# 12v-dual_and_5v_v1_2.net
KiCad netlist of a schematic drawn in EAGLE
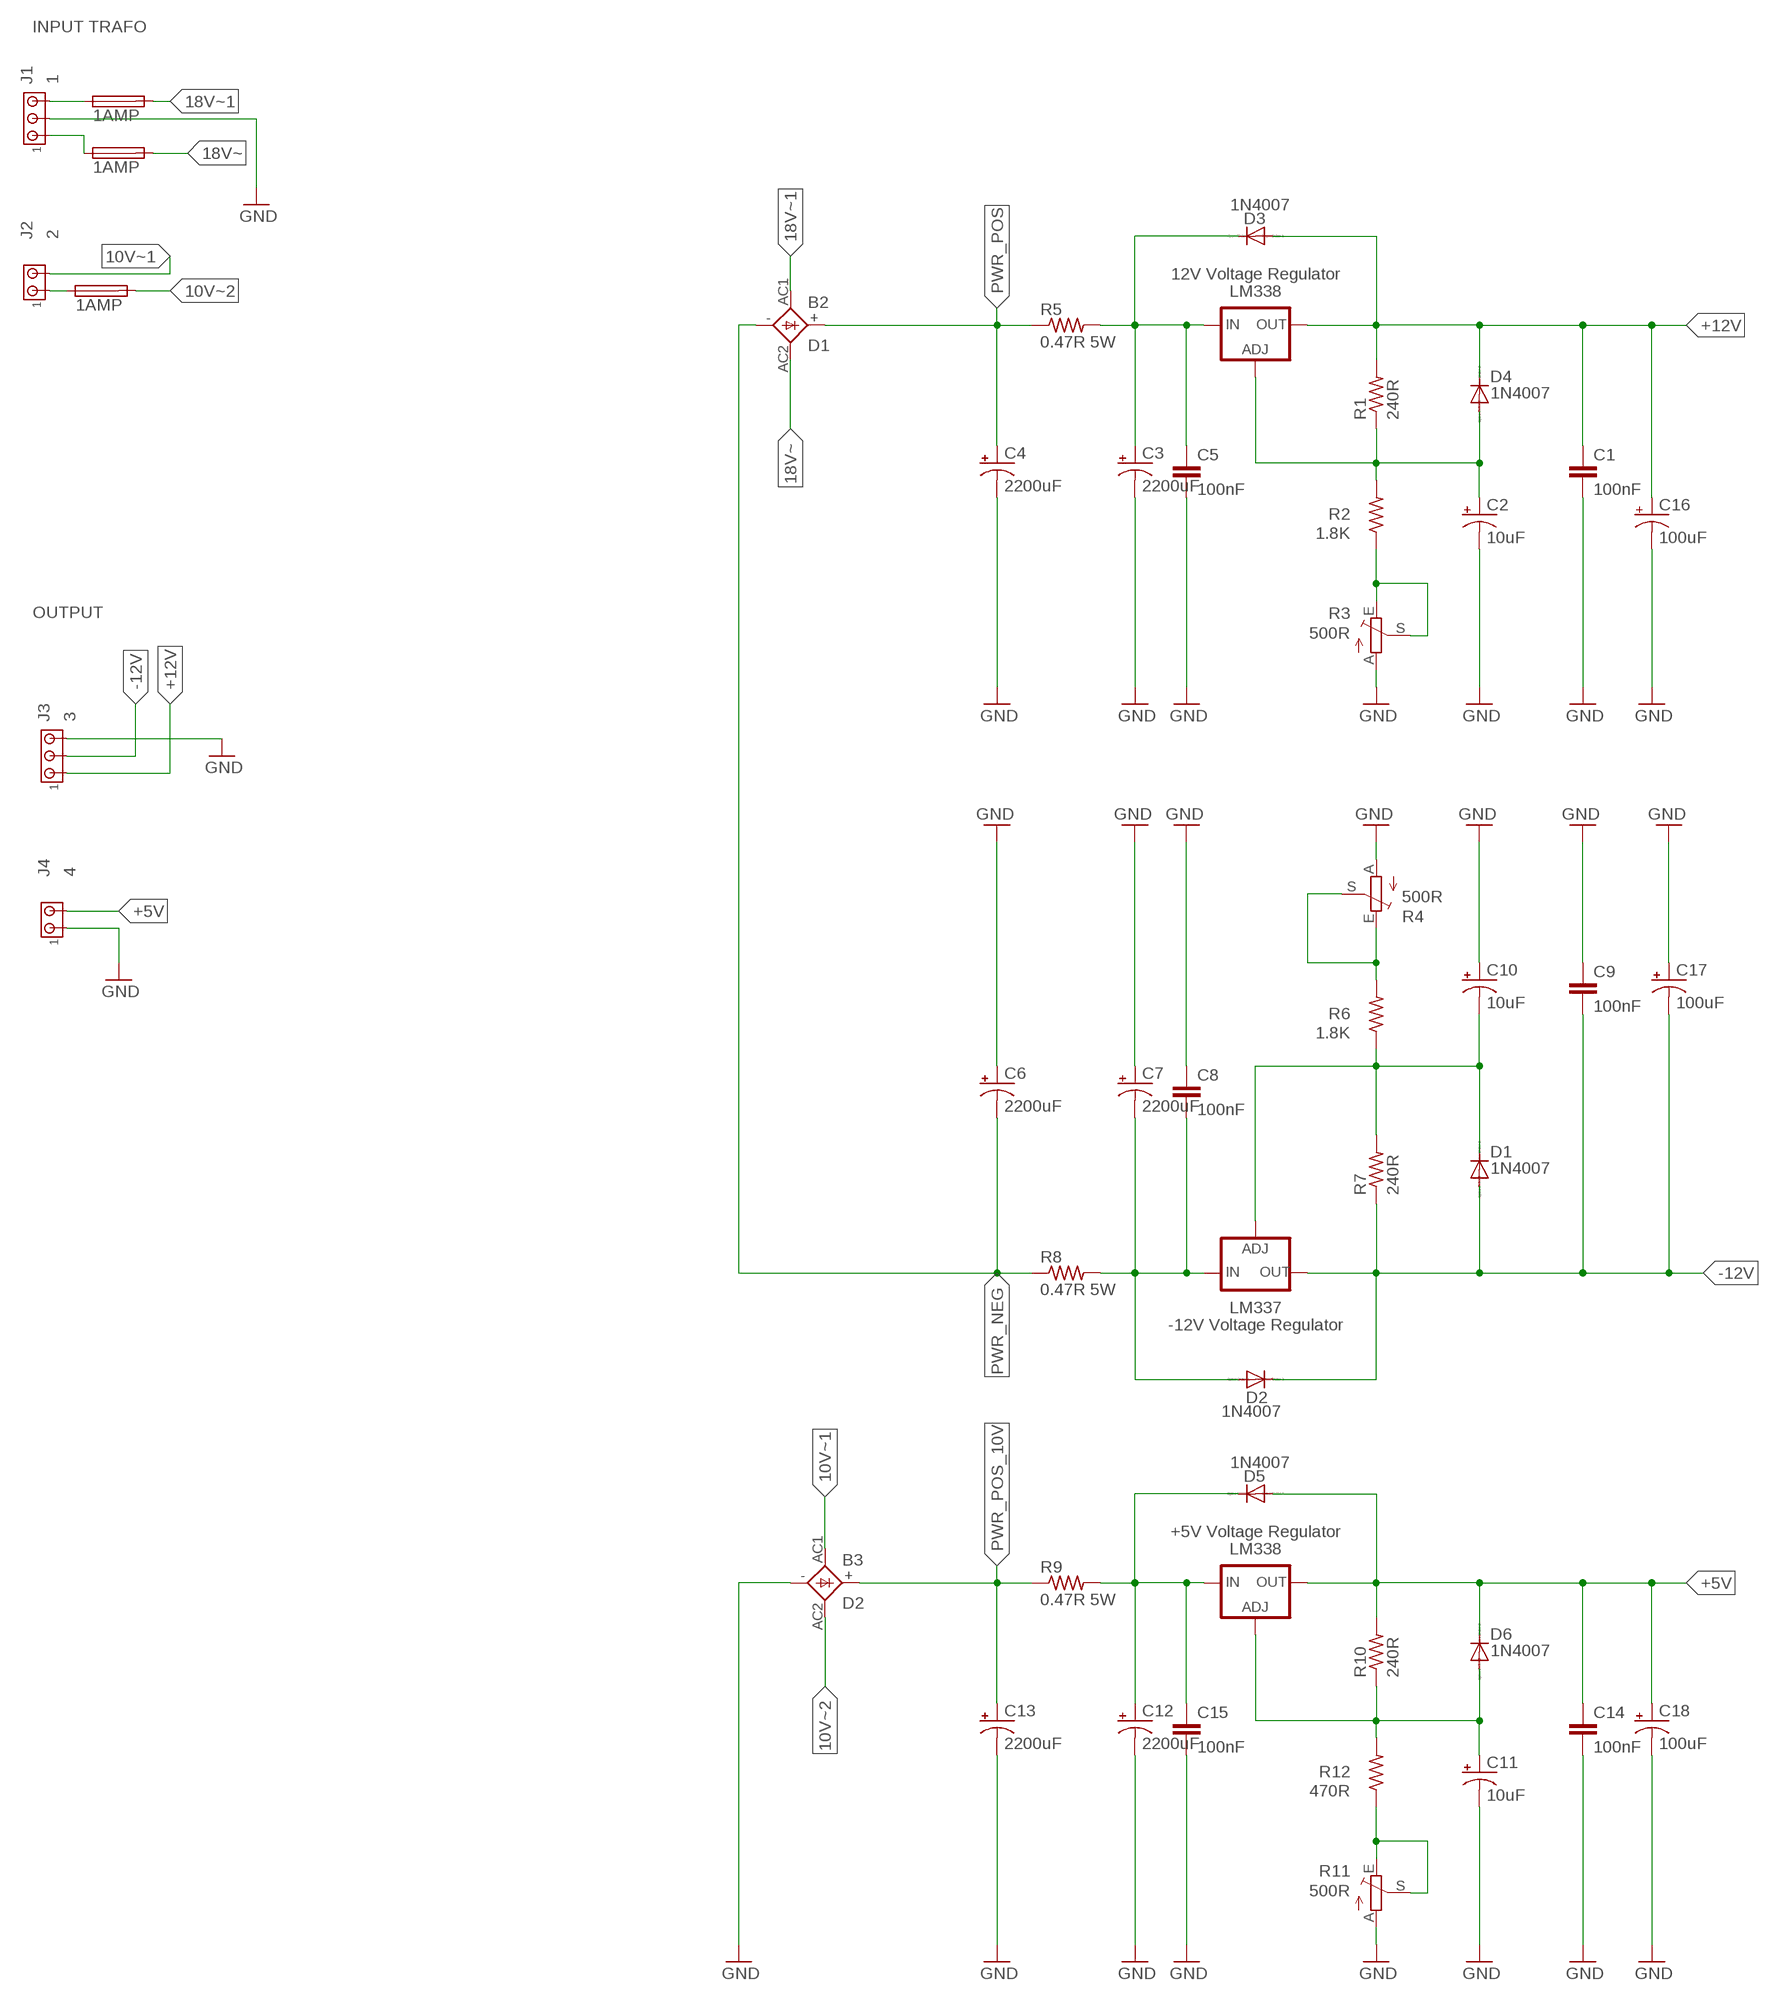
[diagram p0: schematic, sheet 1]

(export (version "E")
  (design (tool "Eeschema 10.0.6"))
  (components
    (comp (ref "B2")
      (value "D1")
      (footprint "eagle-import:FB15")
      (libsource (lib "eagle-import") (part "FB15"))
    )
    (comp (ref "B3")
      (value "D2")
      (footprint "eagle-import:FB15")
      (libsource (lib "eagle-import") (part "FB15"))
    )
    (comp (ref "C1")
      (value "100nF")
      (footprint "eagle-import:C050-025X075")
      (libsource (lib "eagle-import") (part "C-EU050-025X075"))
    )
    (comp (ref "C2")
      (value "10uF")
      (footprint "eagle-import:E2-5")
      (libsource (lib "eagle-import") (part "CPOL-USE2-5"))
    )
    (comp (ref "C3")
      (value "2200uF")
      (footprint "eagle-import:E5-13")
      (libsource (lib "eagle-import") (part "CPOL-USE5-13"))
    )
    (comp (ref "C4")
      (value "2200uF")
      (footprint "eagle-import:E5-13")
      (libsource (lib "eagle-import") (part "CPOL-USE5-13"))
    )
    (comp (ref "C5")
      (value "100nF")
      (footprint "eagle-import:C050-025X075")
      (libsource (lib "eagle-import") (part "C-EU050-025X075"))
    )
    (comp (ref "C6")
      (value "2200uF")
      (footprint "eagle-import:E5-13")
      (libsource (lib "eagle-import") (part "CPOL-USE5-13"))
    )
    (comp (ref "C7")
      (value "2200uF")
      (footprint "eagle-import:E5-13")
      (libsource (lib "eagle-import") (part "CPOL-USE5-13"))
    )
    (comp (ref "C8")
      (value "100nF")
      (footprint "eagle-import:C050-025X075")
      (libsource (lib "eagle-import") (part "C-EU050-025X075"))
    )
    (comp (ref "C9")
      (value "100nF")
      (footprint "eagle-import:C050-025X075")
      (libsource (lib "eagle-import") (part "C-EU050-025X075"))
    )
    (comp (ref "C10")
      (value "10uF")
      (footprint "eagle-import:E2-5")
      (libsource (lib "eagle-import") (part "CPOL-USE2-5"))
    )
    (comp (ref "C11")
      (value "10uF")
      (footprint "eagle-import:E2-5")
      (libsource (lib "eagle-import") (part "CPOL-USE2-5"))
    )
    (comp (ref "C12")
      (value "2200uF")
      (footprint "eagle-import:E5-13")
      (libsource (lib "eagle-import") (part "CPOL-USE5-13"))
    )
    (comp (ref "C13")
      (value "2200uF")
      (footprint "eagle-import:E5-13")
      (libsource (lib "eagle-import") (part "CPOL-USE5-13"))
    )
    (comp (ref "C14")
      (value "100nF")
      (footprint "eagle-import:C050-025X075")
      (libsource (lib "eagle-import") (part "C-EU050-025X075"))
    )
    (comp (ref "C15")
      (value "100nF")
      (footprint "eagle-import:C050-025X075")
      (libsource (lib "eagle-import") (part "C-EU050-025X075"))
    )
    (comp (ref "C16")
      (value "100uF")
      (footprint "eagle-import:E2-5")
      (libsource (lib "eagle-import") (part "CPOL-USE2-5"))
    )
    (comp (ref "C17")
      (value "100uF")
      (footprint "eagle-import:E2-5")
      (libsource (lib "eagle-import") (part "CPOL-USE2-5"))
    )
    (comp (ref "C18")
      (value "100uF")
      (footprint "eagle-import:E2-5")
      (libsource (lib "eagle-import") (part "CPOL-USE2-5"))
    )
    (comp (ref "D1")
      (value "1N4007")
      (footprint "eagle-import:DO41-10")
      (libsource (lib "eagle-import") (part "1N4004"))
    )
    (comp (ref "D2")
      (value "1N4007")
      (footprint "eagle-import:DO41-10")
      (libsource (lib "eagle-import") (part "1N4004"))
    )
    (comp (ref "D3")
      (value "1N4007")
      (footprint "eagle-import:DO41-10")
      (libsource (lib "eagle-import") (part "1N4004"))
    )
    (comp (ref "D4")
      (value "1N4007")
      (footprint "eagle-import:DO41-10")
      (libsource (lib "eagle-import") (part "1N4004"))
    )
    (comp (ref "D5")
      (value "1N4007")
      (footprint "eagle-import:DO41-10")
      (libsource (lib "eagle-import") (part "1N4004"))
    )
    (comp (ref "D6")
      (value "1N4007")
      (footprint "eagle-import:DO41-10")
      (libsource (lib "eagle-import") (part "1N4004"))
    )
    (comp (ref "F1")
      (value "1AMP")
      (footprint "eagle-import:SH25")
      (fields (field (name "MF") "SCHURTER") (field (name "MPN") "0031.8211"))
      (libsource (lib "eagle-import") (part "SH25"))
    )
    (comp (ref "F2")
      (value "1AMP")
      (footprint "eagle-import:SH25")
      (fields (field (name "MF") "SCHURTER") (field (name "MPN") "0031.8211"))
      (libsource (lib "eagle-import") (part "SH25"))
    )
    (comp (ref "F3")
      (value "1AMP")
      (footprint "eagle-import:SH25")
      (fields (field (name "MF") "SCHURTER") (field (name "MPN") "0031.8211"))
      (libsource (lib "eagle-import") (part "SH25"))
    )
    (comp (ref "IC1")
      (value "LM337")
      (footprint "eagle-import:337TS")
      (libsource (lib "eagle-import") (part "LM337TS"))
    )
    (comp (ref "IC2")
      (value "LM338")
      (footprint "eagle-import:317TS")
      (fields (field (name "PARTNUMBER") "LM317M"))
      (libsource (lib "eagle-import") (part "LM317TS"))
    )
    (comp (ref "IC3")
      (value "LM317MB")
      (footprint "eagle-import:317TS")
      (fields (field (name "PARTNUMBER") "LM317M"))
      (libsource (lib "eagle-import") (part "LM317TS"))
    )
    (comp (ref "J1")
      (value "1")
      (footprint "eagle-import:1X3MTA")
      (libsource (lib "eagle-import") (part "MTA03-156"))
    )
    (comp (ref "J2")
      (value "2")
      (footprint "eagle-import:1X2MTA")
      (libsource (lib "eagle-import") (part "MTA02-156"))
    )
    (comp (ref "J3")
      (value "3")
      (footprint "eagle-import:1X3MTA")
      (libsource (lib "eagle-import") (part "MTA03-156"))
    )
    (comp (ref "J4")
      (value "4")
      (footprint "eagle-import:1X2MTA")
      (libsource (lib "eagle-import") (part "MTA02-156"))
    )
    (comp (ref "R1")
      (value "240R")
      (footprint "eagle-import:0204_7")
      (libsource (lib "eagle-import") (part "R-US_0204/7"))
    )
    (comp (ref "R2")
      (value "1.8K")
      (footprint "eagle-import:0204_7")
      (libsource (lib "eagle-import") (part "R-US_0204/7"))
    )
    (comp (ref "R3")
      (value "500R")
      (footprint "eagle-import:RJ9W")
      (libsource (lib "eagle-import") (part "TRIM_EU-RJ9W"))
    )
    (comp (ref "R4")
      (value "500R")
      (footprint "eagle-import:RJ9W")
      (libsource (lib "eagle-import") (part "TRIM_EU-RJ9W"))
    )
    (comp (ref "R5")
      (value "0.47R 5W")
      (footprint "eagle-import:0617_17")
      (libsource (lib "eagle-import") (part "R-US_0617/17"))
    )
    (comp (ref "R6")
      (value "1.8K")
      (footprint "eagle-import:0204_7")
      (libsource (lib "eagle-import") (part "R-US_0204/7"))
    )
    (comp (ref "R7")
      (value "240R")
      (footprint "eagle-import:0204_7")
      (libsource (lib "eagle-import") (part "R-US_0204/7"))
    )
    (comp (ref "R8")
      (value "0.47R 5W")
      (footprint "eagle-import:0617_17")
      (libsource (lib "eagle-import") (part "R-US_0617/17"))
    )
    (comp (ref "R9")
      (value "0.47R 5W")
      (footprint "eagle-import:0617_17")
      (libsource (lib "eagle-import") (part "R-US_0617/17"))
    )
    (comp (ref "R10")
      (value "240R")
      (footprint "eagle-import:0204_7")
      (libsource (lib "eagle-import") (part "R-US_0204/7"))
    )
    (comp (ref "R11")
      (value "500R")
      (footprint "eagle-import:RJ9W")
      (libsource (lib "eagle-import") (part "TRIM_EU-RJ9W"))
    )
    (comp (ref "R12")
      (value "470R")
      (footprint "eagle-import:0204_7")
      (libsource (lib "eagle-import") (part "R-US_0204/7"))
    )
  )
  (nets
    (net (code "1") (name "+5V") (class "Default")
      (node (ref "C14") (pin "1") (pinfunction "1_1") (pintype "passive"))
      (node (ref "C18") (pin "+") (pinfunction "+_+") (pintype "passive"))
      (node (ref "D5") (pin "A") (pinfunction "A_A") (pintype "passive"))
      (node (ref "D6") (pin "C") (pinfunction "C_C") (pintype "passive"))
      (node (ref "IC3") (pin "2") (pinfunction "OUT_2") (pintype "passive"))
      (node (ref "J4") (pin "2") (pinfunction "2_2") (pintype "passive"))
      (node (ref "R10") (pin "2") (pinfunction "2_2") (pintype "passive"))
    )
    (net (code "2") (name "+12V") (class "Default")
      (node (ref "C1") (pin "1") (pinfunction "1_1") (pintype "passive"))
      (node (ref "C16") (pin "+") (pinfunction "+_+") (pintype "passive"))
      (node (ref "D3") (pin "A") (pinfunction "A_A") (pintype "passive"))
      (node (ref "D4") (pin "C") (pinfunction "C_C") (pintype "passive"))
      (node (ref "IC2") (pin "2") (pinfunction "OUT_2") (pintype "passive"))
      (node (ref "J3") (pin "1") (pinfunction "1_1") (pintype "passive"))
      (node (ref "R1") (pin "2") (pinfunction "2_2") (pintype "passive"))
    )
    (net (code "3") (name "-12V") (class "Default")
      (node (ref "C17") (pin "-") (pinfunction "-_-") (pintype "passive"))
      (node (ref "C9") (pin "2") (pinfunction "2_2") (pintype "passive"))
      (node (ref "D1") (pin "A") (pinfunction "A_A") (pintype "passive"))
      (node (ref "D2") (pin "C") (pinfunction "C_C") (pintype "passive"))
      (node (ref "IC1") (pin "3") (pinfunction "OUT_3") (pintype "passive"))
      (node (ref "J3") (pin "2") (pinfunction "2_2") (pintype "passive"))
      (node (ref "R7") (pin "1") (pinfunction "1_1") (pintype "passive"))
    )
    (net (code "4") (name "/10V~{1}") (class "Default")
      (node (ref "B3") (pin "AC1") (pinfunction "AC1_AC1") (pintype "passive"))
      (node (ref "J2") (pin "2") (pinfunction "2_2") (pintype "passive"))
    )
    (net (code "5") (name "/10V~{2}") (class "Default")
      (node (ref "B3") (pin "AC2") (pinfunction "AC2_AC2") (pintype "passive"))
      (node (ref "F3") (pin "2") (pinfunction "2_2") (pintype "passive"))
    )
    (net (code "6") (name "/18V~{1}") (class "Default")
      (node (ref "B2") (pin "AC1") (pinfunction "AC1_AC1") (pintype "passive"))
      (node (ref "F1") (pin "2") (pinfunction "2_2") (pintype "passive"))
    )
    (net (code "7") (name "/18V~{}") (class "Default")
      (node (ref "B2") (pin "AC2") (pinfunction "AC2_AC2") (pintype "passive"))
      (node (ref "F2") (pin "2") (pinfunction "2_2") (pintype "passive"))
    )
    (net (code "8") (name "GND") (class "Default")
      (node (ref "B3") (pin "-") (pinfunction "-_-") (pintype "passive"))
      (node (ref "C1") (pin "2") (pinfunction "2_2") (pintype "passive"))
      (node (ref "C10") (pin "+") (pinfunction "+_+") (pintype "passive"))
      (node (ref "C11") (pin "-") (pinfunction "-_-") (pintype "passive"))
      (node (ref "C12") (pin "-") (pinfunction "-_-") (pintype "passive"))
      (node (ref "C13") (pin "-") (pinfunction "-_-") (pintype "passive"))
      (node (ref "C14") (pin "2") (pinfunction "2_2") (pintype "passive"))
      (node (ref "C15") (pin "2") (pinfunction "2_2") (pintype "passive"))
      (node (ref "C16") (pin "-") (pinfunction "-_-") (pintype "passive"))
      (node (ref "C17") (pin "+") (pinfunction "+_+") (pintype "passive"))
      (node (ref "C18") (pin "-") (pinfunction "-_-") (pintype "passive"))
      (node (ref "C2") (pin "-") (pinfunction "-_-") (pintype "passive"))
      (node (ref "C3") (pin "-") (pinfunction "-_-") (pintype "passive"))
      (node (ref "C4") (pin "-") (pinfunction "-_-") (pintype "passive"))
      (node (ref "C5") (pin "2") (pinfunction "2_2") (pintype "passive"))
      (node (ref "C6") (pin "+") (pinfunction "+_+") (pintype "passive"))
      (node (ref "C7") (pin "+") (pinfunction "+_+") (pintype "passive"))
      (node (ref "C8") (pin "1") (pinfunction "1_1") (pintype "passive"))
      (node (ref "C9") (pin "1") (pinfunction "1_1") (pintype "passive"))
      (node (ref "J1") (pin "2") (pinfunction "2_2") (pintype "passive"))
      (node (ref "J3") (pin "3") (pinfunction "3_3") (pintype "passive"))
      (node (ref "J4") (pin "1") (pinfunction "1_1") (pintype "passive"))
      (node (ref "R11") (pin "A") (pinfunction "A_A") (pintype "passive"))
      (node (ref "R3") (pin "A") (pinfunction "A_A") (pintype "passive"))
      (node (ref "R4") (pin "A") (pinfunction "A_A") (pintype "passive"))
    )
    (net (code "9") (name "Net-(F1-Pad1)") (class "Default")
      (node (ref "F1") (pin "1") (pinfunction "1_1") (pintype "passive"))
      (node (ref "J1") (pin "3") (pinfunction "3_3") (pintype "passive"))
    )
    (net (code "10") (name "Net-(F2-Pad1)") (class "Default")
      (node (ref "F2") (pin "1") (pinfunction "1_1") (pintype "passive"))
      (node (ref "J1") (pin "1") (pinfunction "1_1") (pintype "passive"))
    )
    (net (code "11") (name "Net-(F3-Pad1)") (class "Default")
      (node (ref "F3") (pin "1") (pinfunction "1_1") (pintype "passive"))
      (node (ref "J2") (pin "1") (pinfunction "1_1") (pintype "passive"))
    )
    (net (code "12") (name "Net-(IC1-ADJ)") (class "Default")
      (node (ref "C10") (pin "-") (pinfunction "-_-") (pintype "passive"))
      (node (ref "D1") (pin "C") (pinfunction "C_C") (pintype "passive"))
      (node (ref "IC1") (pin "1") (pinfunction "ADJ_1") (pintype "input"))
      (node (ref "R6") (pin "1") (pinfunction "1_1") (pintype "passive"))
      (node (ref "R7") (pin "2") (pinfunction "2_2") (pintype "passive"))
    )
    (net (code "13") (name "Net-(IC1-IN)") (class "Default")
      (node (ref "C7") (pin "-") (pinfunction "-_-") (pintype "passive"))
      (node (ref "C8") (pin "2") (pinfunction "2_2") (pintype "passive"))
      (node (ref "D2") (pin "A") (pinfunction "A_A") (pintype "passive"))
      (node (ref "IC1") (pin "2") (pinfunction "IN_2") (pintype "input"))
      (node (ref "R8") (pin "2") (pinfunction "2_2") (pintype "passive"))
    )
    (net (code "14") (name "Net-(IC2-ADJ)") (class "Default")
      (node (ref "C2") (pin "+") (pinfunction "+_+") (pintype "passive"))
      (node (ref "D4") (pin "A") (pinfunction "A_A") (pintype "passive"))
      (node (ref "IC2") (pin "1") (pinfunction "ADJ_1") (pintype "input"))
      (node (ref "R1") (pin "1") (pinfunction "1_1") (pintype "passive"))
      (node (ref "R2") (pin "2") (pinfunction "2_2") (pintype "passive"))
    )
    (net (code "15") (name "Net-(IC2-IN)") (class "Default")
      (node (ref "C3") (pin "+") (pinfunction "+_+") (pintype "passive"))
      (node (ref "C5") (pin "1") (pinfunction "1_1") (pintype "passive"))
      (node (ref "D3") (pin "C") (pinfunction "C_C") (pintype "passive"))
      (node (ref "IC2") (pin "3") (pinfunction "IN_3") (pintype "input"))
      (node (ref "R5") (pin "2") (pinfunction "2_2") (pintype "passive"))
    )
    (net (code "16") (name "Net-(IC3-ADJ)") (class "Default")
      (node (ref "C11") (pin "+") (pinfunction "+_+") (pintype "passive"))
      (node (ref "D6") (pin "A") (pinfunction "A_A") (pintype "passive"))
      (node (ref "IC3") (pin "1") (pinfunction "ADJ_1") (pintype "input"))
      (node (ref "R10") (pin "1") (pinfunction "1_1") (pintype "passive"))
      (node (ref "R12") (pin "2") (pinfunction "2_2") (pintype "passive"))
    )
    (net (code "17") (name "Net-(IC3-IN)") (class "Default")
      (node (ref "C12") (pin "+") (pinfunction "+_+") (pintype "passive"))
      (node (ref "C15") (pin "1") (pinfunction "1_1") (pintype "passive"))
      (node (ref "D5") (pin "C") (pinfunction "C_C") (pintype "passive"))
      (node (ref "IC3") (pin "3") (pinfunction "IN_3") (pintype "input"))
      (node (ref "R9") (pin "2") (pinfunction "2_2") (pintype "passive"))
    )
    (net (code "18") (name "Net-(R2-Pad1)") (class "Default")
      (node (ref "R2") (pin "1") (pinfunction "1_1") (pintype "passive"))
      (node (ref "R3") (pin "E") (pinfunction "E_E") (pintype "passive"))
      (node (ref "R3") (pin "S") (pinfunction "S_S") (pintype "passive"))
    )
    (net (code "19") (name "Net-(R4-PadE)") (class "Default")
      (node (ref "R4") (pin "E") (pinfunction "E_E") (pintype "passive"))
      (node (ref "R4") (pin "S") (pinfunction "S_S") (pintype "passive"))
      (node (ref "R6") (pin "2") (pinfunction "2_2") (pintype "passive"))
    )
    (net (code "20") (name "Net-(R11-PadE)") (class "Default")
      (node (ref "R11") (pin "E") (pinfunction "E_E") (pintype "passive"))
      (node (ref "R11") (pin "S") (pinfunction "S_S") (pintype "passive"))
      (node (ref "R12") (pin "1") (pinfunction "1_1") (pintype "passive"))
    )
    (net (code "21") (name "PWR_NEG") (class "Default")
      (node (ref "B2") (pin "-") (pinfunction "-_-") (pintype "passive"))
      (node (ref "C6") (pin "-") (pinfunction "-_-") (pintype "passive"))
      (node (ref "R8") (pin "1") (pinfunction "1_1") (pintype "passive"))
    )
    (net (code "22") (name "PWR_POS") (class "Default")
      (node (ref "B2") (pin "+") (pinfunction "+_+") (pintype "passive"))
      (node (ref "C4") (pin "+") (pinfunction "+_+") (pintype "passive"))
      (node (ref "R5") (pin "1") (pinfunction "1_1") (pintype "passive"))
    )
    (net (code "23") (name "PWR_POS_10V") (class "Default")
      (node (ref "B3") (pin "+") (pinfunction "+_+") (pintype "passive"))
      (node (ref "C13") (pin "+") (pinfunction "+_+") (pintype "passive"))
      (node (ref "R9") (pin "1") (pinfunction "1_1") (pintype "passive"))
    )
  )
)
